# vesc_power.net
KiCad netlist of a schematic drawn in Altium Designer
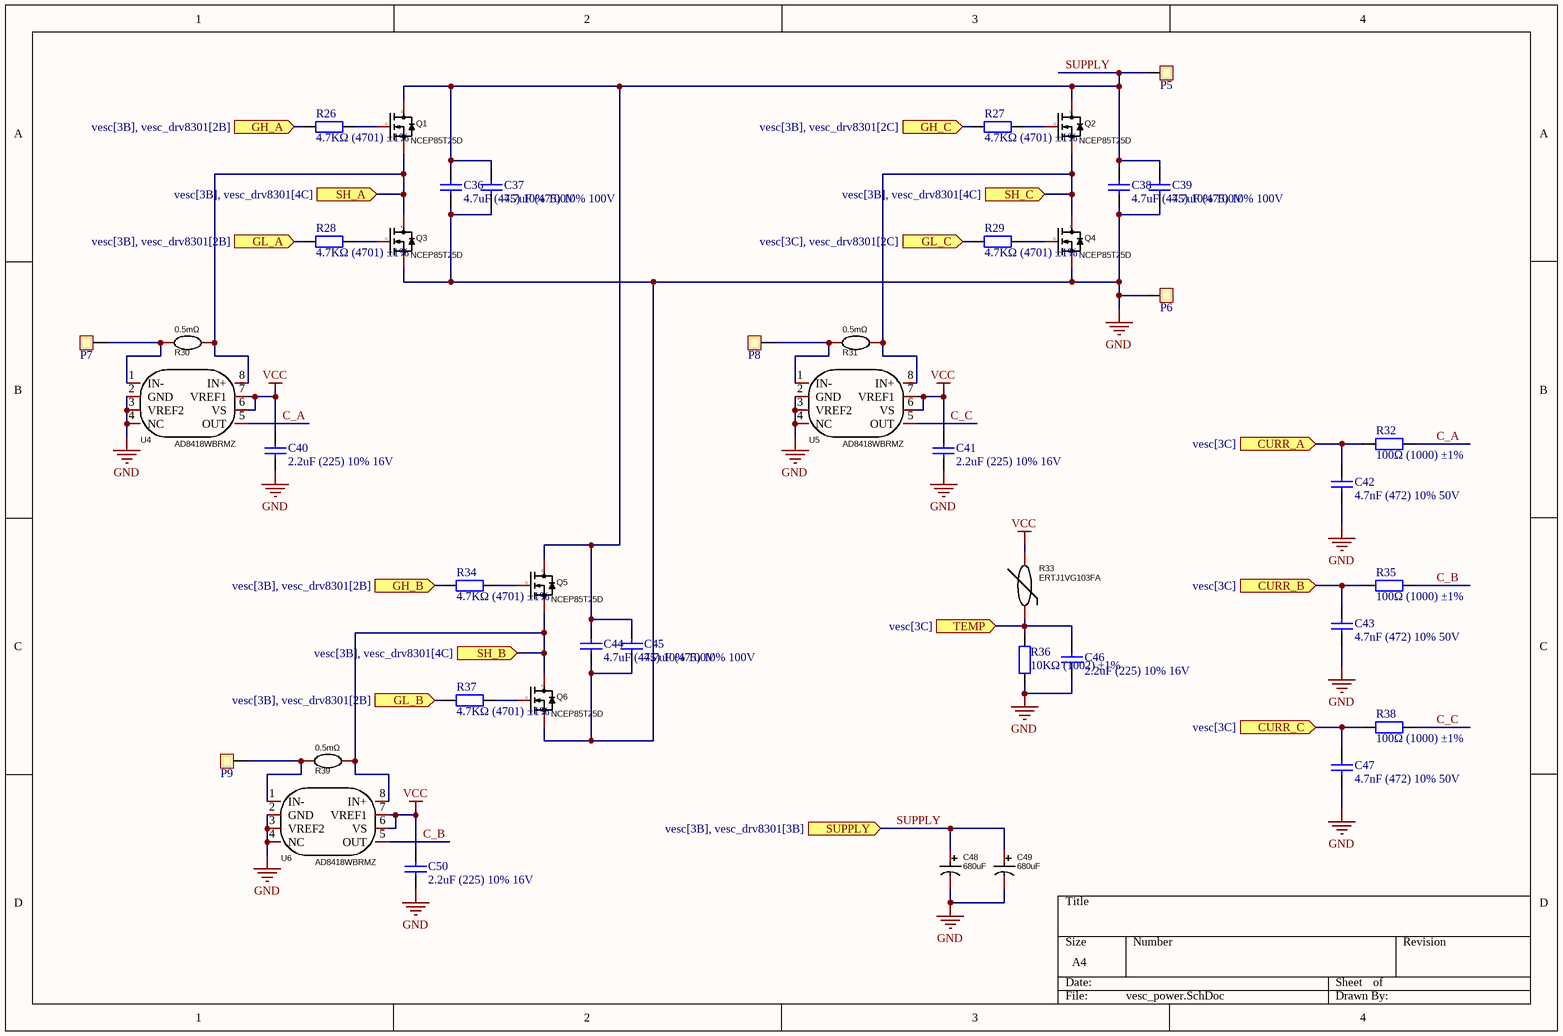
[diagram p0: vesc_power.SchDoc]

(export (version "E")
  (design (tool "Eeschema 10.0.6"))
  (components
    (comp (ref "C36")
      (value "4.7uF (475) 10% 100V")
      (footprint "1210_C")
      (description "贴片电容")
      (libsource (lib "Miscellaneous Devices LC") (part "1206 4.7uF (475) 10% 50V"))
    )
    (comp (ref "C37")
      (value "4.7uF (475) 10% 100V")
      (footprint "1210_C")
      (description "贴片电容")
      (libsource (lib "Miscellaneous Devices LC") (part "1206 4.7uF (475) 10% 50V"))
    )
    (comp (ref "C38")
      (value "4.7uF (475) 10% 100V")
      (footprint "1210_C")
      (description "贴片电容")
      (libsource (lib "Miscellaneous Devices LC") (part "1206 4.7uF (475) 10% 50V"))
    )
    (comp (ref "C39")
      (value "4.7uF (475) 10% 100V")
      (footprint "1210_C")
      (description "贴片电容")
      (libsource (lib "Miscellaneous Devices LC") (part "1206 4.7uF (475) 10% 50V"))
    )
    (comp (ref "C40")
      (value "2.2uF (225) 10% 16V")
      (footprint "0603_C")
      (description "贴片电容")
      (libsource (lib "Miscellaneous Devices LC") (part "0603 2.2uF (225) 10% 16V"))
    )
    (comp (ref "C41")
      (value "2.2uF (225) 10% 16V")
      (footprint "0603_C")
      (description "贴片电容")
      (libsource (lib "Miscellaneous Devices LC") (part "0603 2.2uF (225) 10% 16V"))
    )
    (comp (ref "C42")
      (value "4.7nF (472) 10% 50V")
      (footprint "0603_C")
      (description "贴片电容")
      (libsource (lib "Miscellaneous Devices LC") (part "0603 4.7nF (472) 10% 50V"))
    )
    (comp (ref "C43")
      (value "4.7nF (472) 10% 50V")
      (footprint "0603_C")
      (description "贴片电容")
      (libsource (lib "Miscellaneous Devices LC") (part "0603 4.7nF (472) 10% 50V"))
    )
    (comp (ref "C44")
      (value "4.7uF (475) 10% 100V")
      (footprint "1210_C")
      (description "贴片电容")
      (libsource (lib "Miscellaneous Devices LC") (part "1206 4.7uF (475) 10% 50V"))
    )
    (comp (ref "C45")
      (value "4.7uF (475) 10% 100V")
      (footprint "1210_C")
      (description "贴片电容")
      (libsource (lib "Miscellaneous Devices LC") (part "1206 4.7uF (475) 10% 50V"))
    )
    (comp (ref "C46")
      (value "2.2uF (225) 10% 16V")
      (footprint "0603_C")
      (description "贴片电容")
      (libsource (lib "Miscellaneous Devices LC") (part "0603 2.2uF (225) 10% 16V"))
    )
    (comp (ref "C47")
      (value "4.7nF (472) 10% 50V")
      (footprint "0603_C")
      (description "贴片电容")
      (libsource (lib "Miscellaneous Devices LC") (part "0603 4.7nF (472) 10% 50V"))
    )
    (comp (ref "C48")
      (value "680uF")
      (footprint "CAP-TH_BD12.5-P5.00-D0.6-FD")
      (fields
        (field (name "MANUFACTURER") "AISHI(艾华集团)")
        (field (name "MANUFACTURER PART") "ERR1JM681W25OT")
        (field (name "TOLERANCE") "±20%")
      )
      (libsource (lib "vesc") (part "ERR1JM681W25OT"))
    )
    (comp (ref "C49")
      (value "680uF")
      (footprint "CAP-TH_BD12.5-P5.00-D0.6-FD")
      (fields
        (field (name "MANUFACTURER") "AISHI(艾华集团)")
        (field (name "MANUFACTURER PART") "ERR1JM681W25OT")
        (field (name "TOLERANCE") "±20%")
      )
      (libsource (lib "vesc") (part "ERR1JM681W25OT"))
    )
    (comp (ref "C50")
      (value "2.2uF (225) 10% 16V")
      (footprint "0603_C")
      (description "贴片电容")
      (libsource (lib "Miscellaneous Devices LC") (part "0603 2.2uF (225) 10% 16V"))
    )
    (comp (ref "P5")
      (value "PAD")
      (footprint "PAD")
      (fields (field (name "MANUFACTURER") "AMASS(艾迈斯)") (field (name "MANUFACTURER PART") "XT30U-M"))
      (libsource (lib "") (part "PAD_2"))
    )
    (comp (ref "P6")
      (value "PAD")
      (footprint "PAD")
      (fields (field (name "MANUFACTURER") "AMASS(艾迈斯)") (field (name "MANUFACTURER PART") "XT30U-M"))
      (libsource (lib "") (part "PAD_1"))
    )
    (comp (ref "P7")
      (value "PAD")
      (footprint "PAD")
      (fields (field (name "MANUFACTURER") "AMASS(艾迈斯)") (field (name "MANUFACTURER PART") "XT30U-M"))
      (libsource (lib "vesc") (part "PAD"))
    )
    (comp (ref "P8")
      (value "PAD")
      (footprint "PAD")
      (fields (field (name "MANUFACTURER") "AMASS(艾迈斯)") (field (name "MANUFACTURER PART") "XT30U-M"))
      (libsource (lib "vesc") (part "PAD"))
    )
    (comp (ref "P9")
      (value "PAD")
      (footprint "PAD")
      (fields (field (name "MANUFACTURER") "AMASS(艾迈斯)") (field (name "MANUFACTURER PART") "XT30U-M"))
      (libsource (lib "vesc") (part "PAD"))
    )
    (comp (ref "Q1")
      (value "NCEP85T25D")
      (footprint "TO-263-2_L10.0-W9.1-P5.08-LS15.2-TL")
      (fields (field (name "MANUFACTURER") "NCE(无锡新洁能)"))
      (libsource (lib "vesc") (part "NCEP85T25D"))
    )
    (comp (ref "Q2")
      (value "NCEP85T25D")
      (footprint "TO-263-2_L10.0-W9.1-P5.08-LS15.2-TL")
      (fields (field (name "MANUFACTURER") "NCE(无锡新洁能)"))
      (libsource (lib "vesc") (part "NCEP85T25D"))
    )
    (comp (ref "Q3")
      (value "NCEP85T25D")
      (footprint "TO-263-2_L10.0-W9.1-P5.08-LS15.2-TL")
      (fields (field (name "MANUFACTURER") "NCE(无锡新洁能)"))
      (libsource (lib "vesc") (part "NCEP85T25D"))
    )
    (comp (ref "Q4")
      (value "NCEP85T25D")
      (footprint "TO-263-2_L10.0-W9.1-P5.08-LS15.2-TL")
      (fields (field (name "MANUFACTURER") "NCE(无锡新洁能)"))
      (libsource (lib "vesc") (part "NCEP85T25D"))
    )
    (comp (ref "Q5")
      (value "NCEP85T25D")
      (footprint "TO-263-2_L10.0-W9.1-P5.08-LS15.2-TL")
      (fields (field (name "MANUFACTURER") "NCE(无锡新洁能)"))
      (libsource (lib "vesc") (part "NCEP85T25D"))
    )
    (comp (ref "Q6")
      (value "NCEP85T25D")
      (footprint "TO-263-2_L10.0-W9.1-P5.08-LS15.2-TL")
      (fields (field (name "MANUFACTURER") "NCE(无锡新洁能)"))
      (libsource (lib "vesc") (part "NCEP85T25D"))
    )
    (comp (ref "R26")
      (value "4.7KΩ (4701) ±1%")
      (footprint "0603_R")
      (description "贴片电阻")
      (libsource (lib "Miscellaneous Devices LC") (part "0603 4.7KΩ (4701) 1%"))
    )
    (comp (ref "R27")
      (value "4.7KΩ (4701) ±1%")
      (footprint "0603_R")
      (description "贴片电阻")
      (libsource (lib "Miscellaneous Devices LC") (part "0603 4.7KΩ (4701) 1%"))
    )
    (comp (ref "R28")
      (value "4.7KΩ (4701) ±1%")
      (footprint "0603_R")
      (description "贴片电阻")
      (libsource (lib "Miscellaneous Devices LC") (part "0603 4.7KΩ (4701) 1%"))
    )
    (comp (ref "R29")
      (value "4.7KΩ (4701) ±1%")
      (footprint "0603_R")
      (description "贴片电阻")
      (libsource (lib "Miscellaneous Devices LC") (part "0603 4.7KΩ (4701) 1%"))
    )
    (comp (ref "R30")
      (value "0.5mΩ")
      (footprint "R3920")
      (fields
        (field (name "MANUFACTURER") "yezhan(业展)")
        (field (name "MANUFACTURER PART") "ASR-M-5-0.5F")
        (field (name "TOLERANCE") "±1%")
      )
      (libsource (lib "vesc") (part "ASR-M-5-0.5F"))
    )
    (comp (ref "R31")
      (value "0.5mΩ")
      (footprint "R3920")
      (fields
        (field (name "MANUFACTURER") "yezhan(业展)")
        (field (name "MANUFACTURER PART") "ASR-M-5-0.5F")
        (field (name "TOLERANCE") "±1%")
      )
      (libsource (lib "vesc") (part "ASR-M-5-0.5F"))
    )
    (comp (ref "R32")
      (value "100Ω (1000) ±1%")
      (footprint "0603_R")
      (description "贴片电阻")
      (libsource (lib "Miscellaneous Devices LC") (part "0603 100Ω (1000) 1%"))
    )
    (comp (ref "R33")
      (value "ERTJ1VG103FA")
      (footprint "R0603")
      (fields (field (name "MANUFACTURER") "PANASONIC(松下)") (field (name "POWER") "100mW"))
      (libsource (lib "vesc") (part "ERTJ1VG103FA"))
    )
    (comp (ref "R34")
      (value "4.7KΩ (4701) ±1%")
      (footprint "0603_R")
      (description "贴片电阻")
      (libsource (lib "Miscellaneous Devices LC") (part "0603 4.7KΩ (4701) 1%"))
    )
    (comp (ref "R35")
      (value "100Ω (1000) ±1%")
      (footprint "0603_R")
      (description "贴片电阻")
      (libsource (lib "Miscellaneous Devices LC") (part "0603 100Ω (1000) 1%"))
    )
    (comp (ref "R36")
      (value "10KΩ (1002) ±1%")
      (footprint "0603_R")
      (description "贴片电阻")
      (libsource (lib "Miscellaneous Devices LC") (part "0603 10KΩ (1002) 1%"))
    )
    (comp (ref "R37")
      (value "4.7KΩ (4701) ±1%")
      (footprint "0603_R")
      (description "贴片电阻")
      (libsource (lib "Miscellaneous Devices LC") (part "0603 4.7KΩ (4701) 1%"))
    )
    (comp (ref "R38")
      (value "100Ω (1000) ±1%")
      (footprint "0603_R")
      (description "贴片电阻")
      (libsource (lib "Miscellaneous Devices LC") (part "0603 100Ω (1000) 1%"))
    )
    (comp (ref "R39")
      (value "0.5mΩ")
      (footprint "R3920")
      (fields
        (field (name "MANUFACTURER") "yezhan(业展)")
        (field (name "MANUFACTURER PART") "ASR-M-5-0.5F")
        (field (name "TOLERANCE") "±1%")
      )
      (libsource (lib "vesc") (part "ASR-M-5-0.5F"))
    )
    (comp (ref "U4")
      (value "AD8418WBRMZ")
      (footprint "MSOP-8_L3.0-W3.0-P0.65-LS5.0-BL")
      (fields (field (name "MANUFACTURER") "ADI(亚德诺)"))
      (libsource (lib "vesc") (part "AD8418WBRMZ"))
    )
    (comp (ref "U5")
      (value "AD8418WBRMZ")
      (footprint "MSOP-8_L3.0-W3.0-P0.65-LS5.0-BL")
      (fields (field (name "MANUFACTURER") "ADI(亚德诺)"))
      (libsource (lib "vesc") (part "AD8418WBRMZ"))
    )
    (comp (ref "U6")
      (value "AD8418WBRMZ")
      (footprint "MSOP-8_L3.0-W3.0-P0.65-LS5.0-BL")
      (fields (field (name "MANUFACTURER") "ADI(亚德诺)"))
      (libsource (lib "vesc") (part "AD8418WBRMZ"))
    )
  )
  (nets
    (net (code "1") (name "/CURR_A") (class "Default")
      (node (ref "C42") (pin "2") (pinfunction "2_2") (pintype "passive"))
      (node (ref "R32") (pin "1") (pinfunction "1_1") (pintype "passive"))
    )
    (net (code "2") (name "/CURR_B") (class "Default")
      (node (ref "C43") (pin "2") (pinfunction "2_2") (pintype "passive"))
      (node (ref "R35") (pin "1") (pinfunction "1_1") (pintype "passive"))
    )
    (net (code "3") (name "/CURR_C") (class "Default")
      (node (ref "C47") (pin "2") (pinfunction "2_2") (pintype "passive"))
      (node (ref "R38") (pin "1") (pinfunction "1_1") (pintype "passive"))
    )
    (net (code "4") (name "/C_A") (class "Default")
      (node (ref "R32") (pin "2") (pinfunction "2_2") (pintype "passive"))
      (node (ref "U4") (pin "5") (pinfunction "OUT_5") (pintype "passive"))
    )
    (net (code "5") (name "/C_B") (class "Default")
      (node (ref "R35") (pin "2") (pinfunction "2_2") (pintype "passive"))
      (node (ref "U6") (pin "5") (pinfunction "OUT_5") (pintype "passive"))
    )
    (net (code "6") (name "/C_C") (class "Default")
      (node (ref "R38") (pin "2") (pinfunction "2_2") (pintype "passive"))
      (node (ref "U5") (pin "5") (pinfunction "OUT_5") (pintype "passive"))
    )
    (net (code "7") (name "/GH_A") (class "Default")
      (node (ref "R26") (pin "1") (pinfunction "1_1") (pintype "passive"))
    )
    (net (code "8") (name "/GH_B") (class "Default")
      (node (ref "R34") (pin "1") (pinfunction "1_1") (pintype "passive"))
    )
    (net (code "9") (name "/GH_C") (class "Default")
      (node (ref "R27") (pin "1") (pinfunction "1_1") (pintype "passive"))
    )
    (net (code "10") (name "/GL_A") (class "Default")
      (node (ref "R28") (pin "1") (pinfunction "1_1") (pintype "passive"))
    )
    (net (code "11") (name "/GL_B") (class "Default")
      (node (ref "R37") (pin "1") (pinfunction "1_1") (pintype "passive"))
    )
    (net (code "12") (name "/GL_C") (class "Default")
      (node (ref "R29") (pin "1") (pinfunction "1_1") (pintype "passive"))
    )
    (net (code "13") (name "/SH_A") (class "Default")
      (node (ref "Q1") (pin "3") (pinfunction "S_3") (pintype "passive"))
      (node (ref "Q3") (pin "4") (pinfunction "D_4") (pintype "passive"))
      (node (ref "R30") (pin "2") (pinfunction "2_2") (pintype "passive"))
      (node (ref "U4") (pin "8") (pinfunction "IN+_8") (pintype "passive"))
    )
    (net (code "14") (name "/SH_B") (class "Default")
      (node (ref "Q5") (pin "3") (pinfunction "S_3") (pintype "passive"))
      (node (ref "Q6") (pin "4") (pinfunction "D_4") (pintype "passive"))
      (node (ref "R39") (pin "2") (pinfunction "2_2") (pintype "passive"))
      (node (ref "U6") (pin "8") (pinfunction "IN+_8") (pintype "passive"))
    )
    (net (code "15") (name "/SH_C") (class "Default")
      (node (ref "Q2") (pin "3") (pinfunction "S_3") (pintype "passive"))
      (node (ref "Q4") (pin "4") (pinfunction "D_4") (pintype "passive"))
      (node (ref "R31") (pin "2") (pinfunction "2_2") (pintype "passive"))
      (node (ref "U5") (pin "8") (pinfunction "IN+_8") (pintype "passive"))
    )
    (net (code "16") (name "/SUPPLY") (class "Default")
      (node (ref "C36") (pin "2") (pinfunction "2_2") (pintype "passive"))
      (node (ref "C37") (pin "2") (pinfunction "2_2") (pintype "passive"))
      (node (ref "C38") (pin "2") (pinfunction "2_2") (pintype "passive"))
      (node (ref "C39") (pin "2") (pinfunction "2_2") (pintype "passive"))
      (node (ref "C44") (pin "2") (pinfunction "2_2") (pintype "passive"))
      (node (ref "C45") (pin "2") (pinfunction "2_2") (pintype "passive"))
      (node (ref "C48") (pin "1") (pinfunction "1_1") (pintype "passive"))
      (node (ref "C49") (pin "1") (pinfunction "1_1") (pintype "passive"))
      (node (ref "P5") (pin "1") (pintype "passive"))
      (node (ref "Q1") (pin "4") (pinfunction "D_4") (pintype "passive"))
      (node (ref "Q2") (pin "4") (pinfunction "D_4") (pintype "passive"))
      (node (ref "Q5") (pin "4") (pinfunction "D_4") (pintype "passive"))
    )
    (net (code "17") (name "/TEMP") (class "Default")
      (node (ref "C46") (pin "2") (pinfunction "2_2") (pintype "passive"))
      (node (ref "R33") (pin "1") (pinfunction "1_1") (pintype "passive"))
      (node (ref "R36") (pin "2") (pinfunction "2_2") (pintype "passive"))
    )
    (net (code "18") (name "GND") (class "Default")
      (node (ref "C36") (pin "1") (pinfunction "1_1") (pintype "passive"))
      (node (ref "C37") (pin "1") (pinfunction "1_1") (pintype "passive"))
      (node (ref "C38") (pin "1") (pinfunction "1_1") (pintype "passive"))
      (node (ref "C39") (pin "1") (pinfunction "1_1") (pintype "passive"))
      (node (ref "C40") (pin "1") (pinfunction "1_1") (pintype "passive"))
      (node (ref "C41") (pin "1") (pinfunction "1_1") (pintype "passive"))
      (node (ref "C42") (pin "1") (pinfunction "1_1") (pintype "passive"))
      (node (ref "C43") (pin "1") (pinfunction "1_1") (pintype "passive"))
      (node (ref "C44") (pin "1") (pinfunction "1_1") (pintype "passive"))
      (node (ref "C45") (pin "1") (pinfunction "1_1") (pintype "passive"))
      (node (ref "C46") (pin "1") (pinfunction "1_1") (pintype "passive"))
      (node (ref "C47") (pin "1") (pinfunction "1_1") (pintype "passive"))
      (node (ref "C48") (pin "2") (pinfunction "2_2") (pintype "passive"))
      (node (ref "C49") (pin "2") (pinfunction "2_2") (pintype "passive"))
      (node (ref "C50") (pin "1") (pinfunction "1_1") (pintype "passive"))
      (node (ref "P6") (pin "1") (pintype "power_in"))
      (node (ref "Q3") (pin "3") (pinfunction "S_3") (pintype "passive"))
      (node (ref "Q4") (pin "3") (pinfunction "S_3") (pintype "passive"))
      (node (ref "Q6") (pin "3") (pinfunction "S_3") (pintype "passive"))
      (node (ref "R36") (pin "1") (pinfunction "1_1") (pintype "passive"))
      (node (ref "U4") (pin "2") (pinfunction "GND_2") (pintype "passive"))
      (node (ref "U4") (pin "3") (pinfunction "VREF2_3") (pintype "passive"))
      (node (ref "U4") (pin "4") (pinfunction "NC_4") (pintype "passive"))
      (node (ref "U5") (pin "2") (pinfunction "GND_2") (pintype "passive"))
      (node (ref "U5") (pin "3") (pinfunction "VREF2_3") (pintype "passive"))
      (node (ref "U5") (pin "4") (pinfunction "NC_4") (pintype "passive"))
      (node (ref "U6") (pin "2") (pinfunction "GND_2") (pintype "passive"))
      (node (ref "U6") (pin "3") (pinfunction "VREF2_3") (pintype "passive"))
      (node (ref "U6") (pin "4") (pinfunction "NC_4") (pintype "passive"))
    )
    (net (code "19") (name "Net-(Q1-G)") (class "Default")
      (node (ref "Q1") (pin "1") (pinfunction "G_1") (pintype "passive"))
      (node (ref "R26") (pin "2") (pinfunction "2_2") (pintype "passive"))
    )
    (net (code "20") (name "Net-(Q2-G)") (class "Default")
      (node (ref "Q2") (pin "1") (pinfunction "G_1") (pintype "passive"))
      (node (ref "R27") (pin "2") (pinfunction "2_2") (pintype "passive"))
    )
    (net (code "21") (name "Net-(Q3-G)") (class "Default")
      (node (ref "Q3") (pin "1") (pinfunction "G_1") (pintype "passive"))
      (node (ref "R28") (pin "2") (pinfunction "2_2") (pintype "passive"))
    )
    (net (code "22") (name "Net-(Q4-G)") (class "Default")
      (node (ref "Q4") (pin "1") (pinfunction "G_1") (pintype "passive"))
      (node (ref "R29") (pin "2") (pinfunction "2_2") (pintype "passive"))
    )
    (net (code "23") (name "Net-(Q5-G)") (class "Default")
      (node (ref "Q5") (pin "1") (pinfunction "G_1") (pintype "passive"))
      (node (ref "R34") (pin "2") (pinfunction "2_2") (pintype "passive"))
    )
    (net (code "24") (name "Net-(Q6-G)") (class "Default")
      (node (ref "Q6") (pin "1") (pinfunction "G_1") (pintype "passive"))
      (node (ref "R37") (pin "2") (pinfunction "2_2") (pintype "passive"))
    )
    (net (code "25") (name "Net-(U4-IN-)") (class "Default")
      (node (ref "P7") (pin "1") (pintype "power_in"))
      (node (ref "R30") (pin "1") (pinfunction "1_1") (pintype "passive"))
      (node (ref "U4") (pin "1") (pinfunction "IN-_1") (pintype "passive"))
    )
    (net (code "26") (name "Net-(U5-IN-)") (class "Default")
      (node (ref "P8") (pin "1") (pintype "power_in"))
      (node (ref "R31") (pin "1") (pinfunction "1_1") (pintype "passive"))
      (node (ref "U5") (pin "1") (pinfunction "IN-_1") (pintype "passive"))
    )
    (net (code "27") (name "Net-(U6-IN-)") (class "Default")
      (node (ref "P9") (pin "1") (pintype "power_in"))
      (node (ref "R39") (pin "1") (pinfunction "1_1") (pintype "passive"))
      (node (ref "U6") (pin "1") (pinfunction "IN-_1") (pintype "passive"))
    )
    (net (code "28") (name "VCC") (class "Default")
      (node (ref "C40") (pin "2") (pinfunction "2_2") (pintype "passive"))
      (node (ref "C41") (pin "2") (pinfunction "2_2") (pintype "passive"))
      (node (ref "C50") (pin "2") (pinfunction "2_2") (pintype "passive"))
      (node (ref "R33") (pin "2") (pinfunction "2_2") (pintype "passive"))
      (node (ref "U4") (pin "6") (pinfunction "VS_6") (pintype "passive"))
      (node (ref "U4") (pin "7") (pinfunction "VREF1_7") (pintype "passive"))
      (node (ref "U5") (pin "6") (pinfunction "VS_6") (pintype "passive"))
      (node (ref "U5") (pin "7") (pinfunction "VREF1_7") (pintype "passive"))
      (node (ref "U6") (pin "6") (pinfunction "VS_6") (pintype "passive"))
      (node (ref "U6") (pin "7") (pinfunction "VREF1_7") (pintype "passive"))
    )
  )
)
